# STM32.net
KiCad netlist of a schematic drawn in Altium Designer
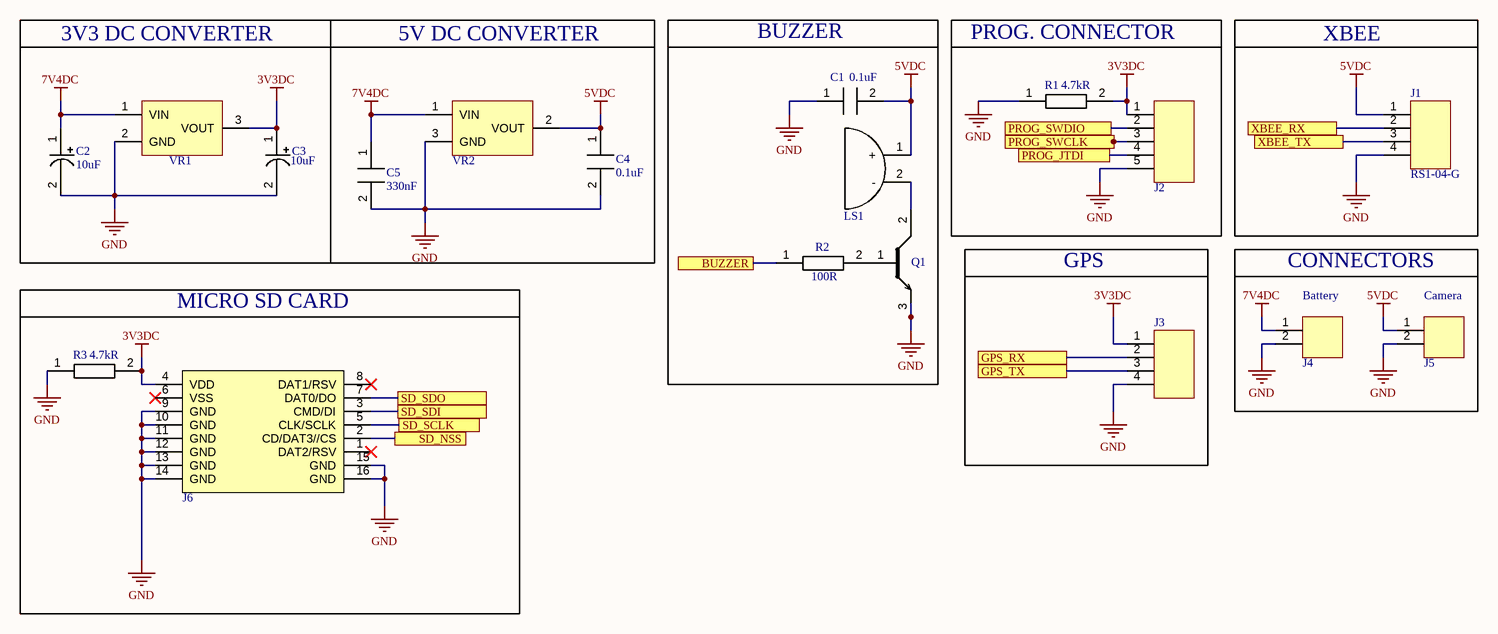
[diagram p0: STM32.SchDoc]

(export (version "E")
  (design (tool "Eeschema 10.0.6"))
  (components
    (comp (ref "C1")
      (value "0.1uF")
      (footprint "CAP_1206")
      (description "Multilayer Ceramic Capacitor, 0.1 uF, 25 V, ± 10%, X7R, 1206 [3216 Metric]")
      (fields
        (field (name "MANUFACTURER") "KEMET")
        (field (name "MANUFACTURER PART NUMBER") "C1206C104K3RACTU")
        (field (name "DESIGNED BY") "Ahmet Can")
      )
      (libsource (lib "AHMET_CAN_KARACAN") (part "CAP CER 0.1uF 1206"))
    )
    (comp (ref "C2")
      (value "10uF")
      (footprint "CAP_1206_TANT")
      (description "Cap Tant Solid 10uF 20V A CASE 20% (3.2 X 1.6 X 1.6mm) SMD 3216-18 3 Ohm 125 C T/R")
      (fields
        (field (name "MANUFACTURER") "KEMET")
        (field (name "MANUFACTURER PART NUMBER") "T494A106M020AT")
      )
      (libsource (lib "AHMET_CAN_KARACAN") (part "CAP TAN 10uF 2306"))
    )
    (comp (ref "C3")
      (value "10uF")
      (footprint "CAP_1206_TANT")
      (description "Cap Tant Solid 10uF 20V A CASE 20% (3.2 X 1.6 X 1.6mm) SMD 3216-18 3 Ohm 125 C T/R")
      (fields
        (field (name "MANUFACTURER") "KEMET")
        (field (name "MANUFACTURER PART NUMBER") "T494A106M020AT")
      )
      (libsource (lib "AHMET_CAN_KARACAN") (part "CAP TAN 10uF 2306"))
    )
    (comp (ref "C4")
      (value "0.1uF")
      (footprint "CAP_1206")
      (description "Multilayer Ceramic Capacitor, 0.1 uF, 25 V, ± 10%, X7R, 1206 [3216 Metric]")
      (fields
        (field (name "MANUFACTURER") "KEMET")
        (field (name "MANUFACTURER PART NUMBER") "C1206C104K3RACTU")
        (field (name "DESIGNED BY") "Ahmet Can")
      )
      (libsource (lib "AHMET_CAN_KARACAN") (part "CAP CER 0.1uF 1206"))
    )
    (comp (ref "C5")
      (value "330nF")
      (footprint "CAP_1206")
      (description "Cap Ceramic 0.33uF 16V X7R 10% SMD 1206 125°C Plastic T/R")
      (fields
        (field (name "MANUFACTURER") "KEMET")
        (field (name "MANUFACTURER PART NUMBER") "C1206C334K4RAC7800")
        (field (name "DESIGNED BY") "Ahmet Can")
      )
      (libsource (lib "AHMET_CAN_KARACAN") (part "CAP CER 330nF 1206"))
    )
    (comp (ref "J1")
      (value "RS1-04-G")
      (footprint "PINHEADER_1X4_TH")
      (description "4 Position Receptacle Connector 0.100\" (2.54mm) Through Hole Gold")
      (fields (field (name "MANUFACTURER") "Adam Equipment"))
      (libsource (lib "AHMET_CAN_KARACAN") (part "J_RS1-04-G"))
    )
    (comp (ref "J2")
      (value "SMH-105-02-L-S")
      (footprint "PINHEADER1X5_RA")
      (description "5 Position Receptacle Connector 0.100\" (2.54mm) Surface Mount, Right Angle Gold")
      (fields (field (name "MANUFACTURER") "Samtec") (field (name "DESIGNED BY") "Ahmet Can"))
      (libsource (lib "AHMET_CAN_KARACAN") (part "J_SMH-105-02-L-S"))
    )
    (comp (ref "J3")
      (value "RS1-04-G")
      (footprint "PINHEADER_1X4_TH")
      (description "4 Position Receptacle Connector 0.100\" (2.54mm) Through Hole Gold")
      (fields (field (name "MANUFACTURER") "Adam Equipment"))
      (libsource (lib "AHMET_CAN_KARACAN") (part "J_RS1-04-G"))
    )
    (comp (ref "J4")
      (value "0393570002")
      (footprint "2P_FEMALE_3.5MM_CONN")
      (description "3.50mm Pitch Beau Eurostyle Fixed Mount PCB Terminal Block, 2 Circuits")
      (fields (field (name "MANUFACTURER") "Molex"))
      (libsource (lib "AHMET_CAN_KARACAN") (part "J_2P_FML_3.5MM"))
    )
    (comp (ref "J5")
      (value "0393570002")
      (footprint "2P_FEMALE_3.5MM_CONN")
      (description "3.50mm Pitch Beau Eurostyle Fixed Mount PCB Terminal Block, 2 Circuits")
      (fields (field (name "MANUFACTURER") "Molex"))
      (libsource (lib "AHMET_CAN_KARACAN") (part "J_2P_FML_3.5MM"))
    )
    (comp (ref "J6")
      (value "2201778-1")
      (footprint "MICRO_SD")
      (description "Conn Memory Card RCP 8 POS 1.1mm Solder RA SMD 0.5A/Contact T/R")
      (fields (field (name "MANUFACTURER") "TE Connectivity") (field (name "DESIGNED BY") "Ahmet Can"))
      (libsource (lib "AHMET_CAN_KARACAN") (part "J_2201778-1"))
    )
    (comp (ref "LS1")
      (value "CMI-9605-0580T")
      (footprint "CMI-9605")
      (description "9.6 mm, 5 Vdc, 80 dB, Through Hole, Driving Circuit, Magnetic Audio Indicator Buzzer")
      (fields (field (name "MANUFACTURER") "CUI") (field (name "DESIGNED BY") "Ahmet Can"))
      (libsource (lib "AHMET_CAN_KARACAN") (part "LS_CMI-9605-0580T"))
    )
    (comp (ref "Q1")
      (value "MMBT3904-7-F")
      (footprint "SOT_23_3")
      (description "Transistor General Purpose BJT NPN 40 Volt 0.2A Automotive 3-Pin SOT-23-3")
      (fields (field (name "MANUFACTURER") "Diodes Zetex") (field (name "DESIGNED BY") "Ahmet Can"))
      (libsource (lib "AHMET_CAN_KARACAN") (part "Q_MMBT3904-7-F"))
    )
    (comp (ref "R1")
      (value "4.7kR")
      (footprint "RE_1206")
      (description "SMD Chip Resistor, 4.7 kOhm, ± 1%, 250 mW, 1206 [3216 Metric], Thick Film, General Purpose")
      (fields
        (field (name "MANUFACTURER") "Yageo")
        (field (name "MANUFACTURER PART NUMBER") "RC1206FR-074K7L")
        (field (name "DESIGNED BY") "Ahmet Can")
      )
      (libsource (lib "AHMET_CAN_KARACAN") (part "RES 4K7 1206"))
    )
    (comp (ref "R2")
      (value "100R")
      (footprint "RE_0603")
      (description "Res Thick Film 0603 100 Ohm 5% 1/10W ±100ppm/°C Molded SMD SMD Paper T/R")
      (fields
        (field (name "MANUFACTURER") "Yageo")
        (field (name "MANUFACTURER PART NUMBER") "RC0603JR-07100RL")
        (field (name "DESIGNED BY") "Ahmet Can")
      )
      (libsource (lib "AHMET_CAN_KARACAN") (part "RES 100 0603"))
    )
    (comp (ref "R3")
      (value "4.7kR")
      (footprint "RE_1206")
      (description "SMD Chip Resistor, 4.7 kOhm, ± 1%, 250 mW, 1206 [3216 Metric], Thick Film, General Purpose")
      (fields
        (field (name "MANUFACTURER") "Yageo")
        (field (name "MANUFACTURER PART NUMBER") "RC1206FR-074K7L")
        (field (name "DESIGNED BY") "Ahmet Can")
      )
      (libsource (lib "AHMET_CAN_KARACAN") (part "RES 4K7 1206"))
    )
    (comp (ref "VR1")
      (value "LD1117V33")
      (footprint "DPAK_TO-252-3")
      (description "LDO Regulator Pos 3.3V 1.3A 3-Pin(3+Tab) TO-220AB Tube")
      (fields (field (name "MANUFACTURER") "STMicroelectronics") (field (name "DESIGNED BY") "Ahmet Can"))
      (libsource (lib "AHMET_CAN_KARACAN") (part "VR_LD1086DT33TR"))
    )
    (comp (ref "VR2")
      (value "L7805CDT-TR")
      (footprint "DPAK_TO-252-3")
      (description "IC REG LDO 5V 1.5A DPAK")
      (fields (field (name "MANUFACTURER") "STMicroelectronics") (field (name "DESIGNED BY") "Ahmet Can"))
      (libsource (lib "AHMET_CAN_KARACAN") (part "VR_L7805CDT-TR"))
    )
  )
  (nets
    (net (code "1") (name "/BUZZER") (class "Default") (node (ref "R2") (pin "1") (pintype "passive")))
    (net (code "2") (name "/GPS_RX") (class "Default") (node (ref "J3") (pin "2") (pintype "passive")))
    (net (code "3") (name "/GPS_TX") (class "Default") (node (ref "J3") (pin "3") (pintype "passive")))
    (net (code "4") (name "/PROG_JTDI") (class "Default") (node (ref "J2") (pin "4") (pintype "passive")))
    (net (code "5") (name "/PROG_SWCLK") (class "Default") (node (ref "J2") (pin "3") (pintype "passive")))
    (net (code "6") (name "/PROG_SWDIO") (class "Default") (node (ref "J2") (pin "2") (pintype "passive")))
    (net (code "7") (name "/SD_NSS") (class "Default")
      (node (ref "J6") (pin "2") (pinfunction "CD/DAT3//CS_2") (pintype "passive"))
    )
    (net (code "8") (name "/SD_SCLK") (class "Default")
      (node (ref "J6") (pin "5") (pinfunction "CLK/SCLK_5") (pintype "passive"))
    )
    (net (code "9") (name "/SD_SDI") (class "Default")
      (node (ref "J6") (pin "3") (pinfunction "CMD/DI_3") (pintype "passive"))
    )
    (net (code "10") (name "/SD_SDO") (class "Default")
      (node (ref "J6") (pin "7") (pinfunction "DAT0/DO_7") (pintype "passive"))
    )
    (net (code "11") (name "/XBEE_RX") (class "Default") (node (ref "J1") (pin "2") (pintype "passive")))
    (net (code "12") (name "/XBEE_TX") (class "Default") (node (ref "J1") (pin "3") (pintype "passive")))
    (net (code "13") (name "3V3DC") (class "Default")
      (node (ref "C3") (pin "1") (pintype "passive"))
      (node (ref "J2") (pin "1") (pintype "passive"))
      (node (ref "J3") (pin "1") (pintype "passive"))
      (node (ref "J6") (pin "4") (pinfunction "VDD_4") (pintype "passive"))
      (node (ref "R1") (pin "2") (pintype "passive"))
      (node (ref "R3") (pin "2") (pintype "passive"))
      (node (ref "VR1") (pin "3") (pinfunction "VOUT_3") (pintype "passive"))
    )
    (net (code "14") (name "5VDC") (class "Default")
      (node (ref "C1") (pin "2") (pintype "passive"))
      (node (ref "C4") (pin "1") (pintype "passive"))
      (node (ref "J1") (pin "1") (pintype "passive"))
      (node (ref "J5") (pin "1") (pintype "passive"))
      (node (ref "LS1") (pin "1") (pinfunction "+_1") (pintype "passive"))
      (node (ref "VR2") (pin "2") (pinfunction "VOUT_2") (pintype "passive"))
    )
    (net (code "15") (name "7V4DC") (class "Default")
      (node (ref "C2") (pin "1") (pintype "passive"))
      (node (ref "C5") (pin "1") (pintype "passive"))
      (node (ref "J4") (pin "1") (pintype "passive"))
      (node (ref "VR1") (pin "1") (pinfunction "VIN_1") (pintype "passive"))
      (node (ref "VR2") (pin "1") (pinfunction "VIN_1") (pintype "passive"))
    )
    (net (code "16") (name "GND") (class "Default")
      (node (ref "C1") (pin "1") (pintype "passive"))
      (node (ref "C2") (pin "2") (pintype "passive"))
      (node (ref "C3") (pin "2") (pintype "passive"))
      (node (ref "C4") (pin "2") (pintype "passive"))
      (node (ref "C5") (pin "2") (pintype "passive"))
      (node (ref "J1") (pin "4") (pintype "passive"))
      (node (ref "J2") (pin "5") (pintype "passive"))
      (node (ref "J3") (pin "4") (pintype "passive"))
      (node (ref "J4") (pin "2") (pintype "passive"))
      (node (ref "J5") (pin "2") (pintype "passive"))
      (node (ref "J6") (pin "10") (pinfunction "GND_10") (pintype "passive"))
      (node (ref "J6") (pin "11") (pinfunction "GND_11") (pintype "passive"))
      (node (ref "J6") (pin "12") (pinfunction "GND_12") (pintype "passive"))
      (node (ref "J6") (pin "13") (pinfunction "GND_13") (pintype "passive"))
      (node (ref "J6") (pin "14") (pinfunction "GND_14") (pintype "passive"))
      (node (ref "J6") (pin "15") (pinfunction "GND_15") (pintype "passive"))
      (node (ref "J6") (pin "16") (pinfunction "GND_16") (pintype "passive"))
      (node (ref "J6") (pin "9") (pinfunction "GND_9") (pintype "passive"))
      (node (ref "Q1") (pin "3") (pintype "passive"))
      (node (ref "R1") (pin "1") (pintype "passive"))
      (node (ref "R3") (pin "1") (pintype "passive"))
      (node (ref "VR1") (pin "2") (pinfunction "GND_2") (pintype "passive"))
      (node (ref "VR2") (pin "3") (pinfunction "GND_3") (pintype "passive"))
    )
    (net (code "17") (name "Net-(LS1--)") (class "Default")
      (node (ref "LS1") (pin "2") (pinfunction "-_2") (pintype "passive"))
      (node (ref "Q1") (pin "2") (pintype "passive"))
    )
    (net (code "18") (name "Net-(Q1-Pad1)") (class "Default")
      (node (ref "Q1") (pin "1") (pintype "passive"))
      (node (ref "R2") (pin "2") (pintype "passive"))
    )
    (net (code "19") (name "unconnected-(J6-DAT1{slash}RSV-Pad8)") (class "Default")
      (node (ref "J6") (pin "8") (pinfunction "DAT1/RSV_8") (pintype "passive+no_connect"))
    )
    (net (code "20") (name "unconnected-(J6-DAT2{slash}RSV-Pad1)") (class "Default")
      (node (ref "J6") (pin "1") (pinfunction "DAT2/RSV_1") (pintype "passive+no_connect"))
    )
    (net (code "21") (name "unconnected-(J6-VSS-Pad6)") (class "Default")
      (node (ref "J6") (pin "6") (pinfunction "VSS_6") (pintype "passive+no_connect"))
    )
  )
)
